# neopixel_board2.net
KiCad netlist of a schematic drawn in EAGLE
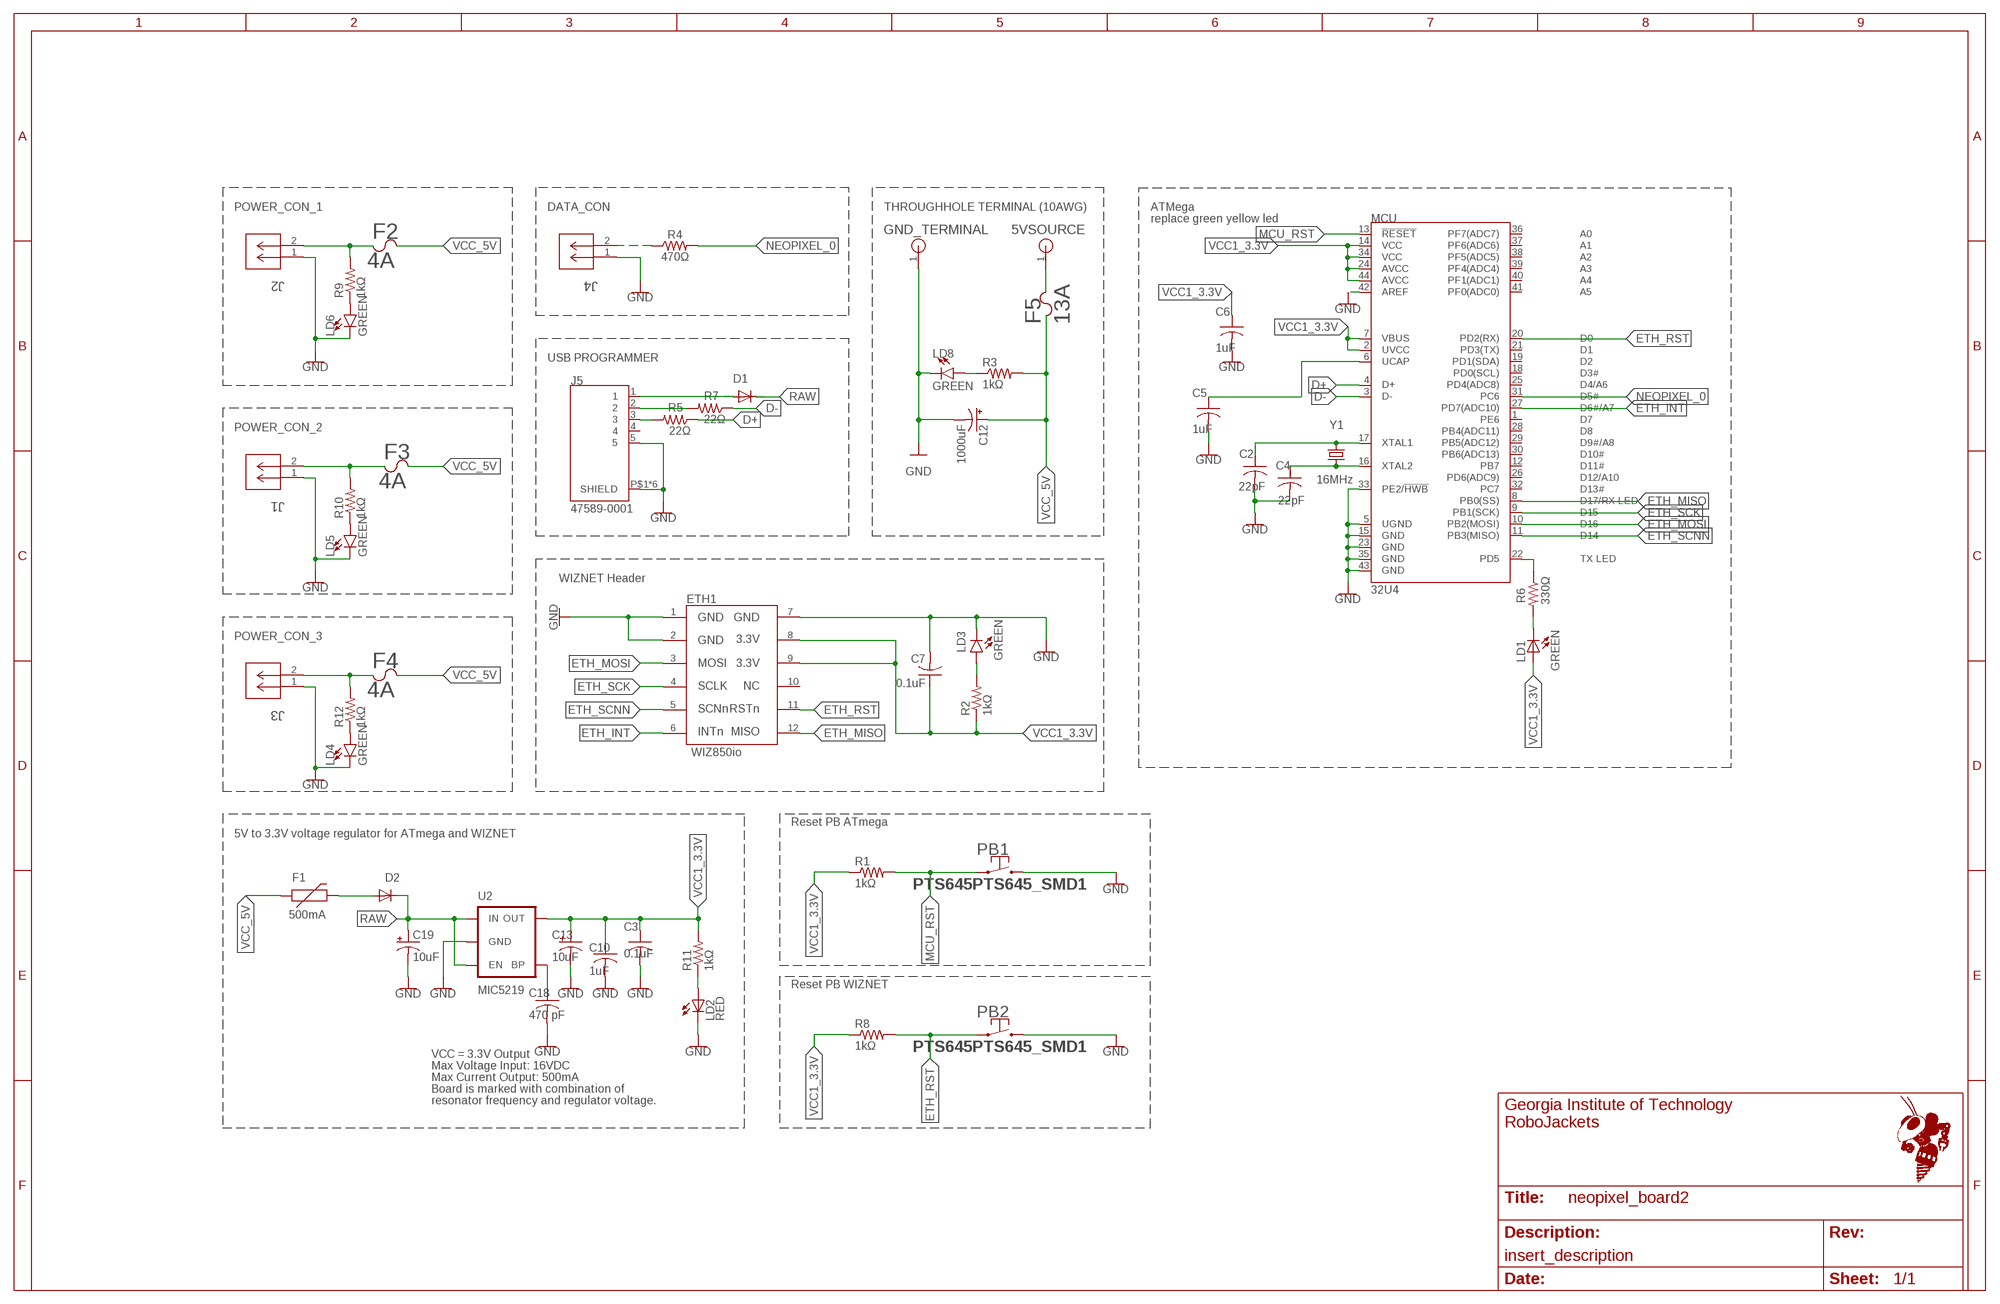
[diagram p0: schematic, sheet 1]

(export (version "E")
  (design (tool "Eeschema 10.0.6"))
  (components
    (comp (ref "5VSOURCE")
      (value "THOLE_SOURCE")
      (footprint "eagle-import:THOLE_SOURCE")
      (libsource (lib "eagle-import") (part "THOLE_SOURCE"))
    )
    (comp (ref "C2")
      (value "22pF")
      (footprint "eagle-import:C0603")
      (libsource (lib "eagle-import") (part "C-USC0603"))
    )
    (comp (ref "C3")
      (value "0.1uF")
      (footprint "eagle-import:C0603")
      (libsource (lib "eagle-import") (part "C-USC0603"))
    )
    (comp (ref "C4")
      (value "22pF")
      (footprint "eagle-import:C0603")
      (libsource (lib "eagle-import") (part "C-USC0603"))
    )
    (comp (ref "C5")
      (value "1uF")
      (footprint "eagle-import:C0603")
      (libsource (lib "eagle-import") (part "C-USC0603"))
    )
    (comp (ref "C6")
      (value "1uF")
      (footprint "eagle-import:C0603")
      (libsource (lib "eagle-import") (part "C-USC0603"))
    )
    (comp (ref "C7")
      (value "0.1uF")
      (footprint "eagle-import:C0603")
      (fields (field (name "SPICEPREFIX") "0.1 uF"))
      (libsource (lib "eagle-import") (part "C-USC0603"))
    )
    (comp (ref "C10")
      (value "1uF")
      (footprint "eagle-import:C0603")
      (libsource (lib "eagle-import") (part "C-USC0603"))
    )
    (comp (ref "C12")
      (value "1000uF")
      (footprint "eagle-import:EIA3216")
      (libsource (lib "eagle-import") (part "CAP_POL1206"))
    )
    (comp (ref "C13")
      (value "10uF")
      (footprint "eagle-import:EIA3216")
      (libsource (lib "eagle-import") (part "CAP_POL1206"))
    )
    (comp (ref "C18")
      (value "470 pF")
      (footprint "eagle-import:C0603")
      (fields (field (name "SPICEPREFIX") "0.1 uF"))
      (libsource (lib "eagle-import") (part "C-USC0603"))
    )
    (comp (ref "C19")
      (value "10uF")
      (footprint "eagle-import:EIA3216")
      (libsource (lib "eagle-import") (part "CAP_POL1206"))
    )
    (comp (ref "D1")
      (value "DIODE-SOD110-W")
      (footprint "eagle-import:SOD110-W")
      (libsource (lib "eagle-import") (part "DIODE-SOD110-W"))
    )
    (comp (ref "D2")
      (value "DIODESOD")
      (footprint "eagle-import:SOD-323")
      (libsource (lib "eagle-import") (part "DIODESOD"))
    )
    (comp (ref "ETH1")
      (value "WIZ850IO")
      (footprint "eagle-import:WIZ850IO")
      (libsource (lib "eagle-import") (part "WIZ850IO"))
    )
    (comp (ref "F1")
      (value "500mA")
      (footprint "eagle-import:PTC-1206")
      (libsource (lib "eagle-import") (part "PTCSMD"))
    )
    (comp (ref "F2")
      (value "4A")
      (footprint "eagle-import:3557-2")
      (fields (field (name "MPN") "3557-2"))
      (libsource (lib "eagle-import") (part "3557-2"))
    )
    (comp (ref "F3")
      (value "4A")
      (footprint "eagle-import:3557-2")
      (fields (field (name "MPN") "3557-2"))
      (libsource (lib "eagle-import") (part "3557-2"))
    )
    (comp (ref "F4")
      (value "4A")
      (footprint "eagle-import:3557-2")
      (fields (field (name "MPN") "3557-2"))
      (libsource (lib "eagle-import") (part "3557-2"))
    )
    (comp (ref "F5")
      (value "13A")
      (footprint "eagle-import:3557-2")
      (fields (field (name "MPN") "3557-2"))
      (libsource (lib "eagle-import") (part "3557-2"))
    )
    (comp (ref "GND_TERMINAL")
      (value "THOLE_SOURCE")
      (footprint "eagle-import:THOLE_SOURCE")
      (libsource (lib "eagle-import") (part "THOLE_SOURCE"))
    )
    (comp (ref "J1")
      (value "SSW-102-02-T-S-RA")
      (footprint "eagle-import:CON2_1X2_TR_SSQ")
      (fields (field (name "MANUFACTURER_PART_NUMBER") "SSW10202TSRA"))
      (libsource (lib "eagle-import") (part "SSW-102-02-T-S-RA"))
    )
    (comp (ref "J2")
      (value "SSW-102-02-T-S-RA")
      (footprint "eagle-import:CON2_1X2_TR_SSQ")
      (fields (field (name "MANUFACTURER_PART_NUMBER") "SSW10202TSRA"))
      (libsource (lib "eagle-import") (part "SSW-102-02-T-S-RA"))
    )
    (comp (ref "J3")
      (value "SSW-102-02-T-S-RA")
      (footprint "eagle-import:CON2_1X2_TR_SSQ")
      (fields (field (name "MANUFACTURER_PART_NUMBER") "SSW10202TSRA"))
      (libsource (lib "eagle-import") (part "SSW-102-02-T-S-RA"))
    )
    (comp (ref "J4")
      (value "SSW-102-02-T-S-RA")
      (footprint "eagle-import:CON2_1X2_TR_SSQ")
      (fields (field (name "MANUFACTURER_PART_NUMBER") "SSW10202TSRA"))
      (libsource (lib "eagle-import") (part "SSW-102-02-T-S-RA"))
    )
    (comp (ref "J5")
      (value "47589-0001")
      (footprint "eagle-import:MOLEX_47589-0001")
      (fields (field (name "MF") "Molex"))
      (libsource (lib "eagle-import") (part "47589-0001"))
    )
    (comp (ref "LD1")
      (value "GREEN")
      (footprint "eagle-import:LED-0603")
      (libsource (lib "eagle-import") (part "LED0603"))
    )
    (comp (ref "LD2")
      (value "RED")
      (footprint "eagle-import:LED-0603")
      (libsource (lib "eagle-import") (part "LED0603"))
    )
    (comp (ref "LD3")
      (value "GREEN")
      (footprint "eagle-import:LED-0603")
      (libsource (lib "eagle-import") (part "LED-GREEN0603"))
    )
    (comp (ref "LD4")
      (value "GREEN")
      (footprint "eagle-import:LED-0603")
      (libsource (lib "eagle-import") (part "LED-GREEN0603"))
    )
    (comp (ref "LD5")
      (value "GREEN")
      (footprint "eagle-import:LED-0603")
      (libsource (lib "eagle-import") (part "LED-GREEN0603"))
    )
    (comp (ref "LD6")
      (value "GREEN")
      (footprint "eagle-import:LED-0603")
      (libsource (lib "eagle-import") (part "LED-GREEN0603"))
    )
    (comp (ref "LD8")
      (value "GREEN")
      (footprint "eagle-import:LED-0603")
      (libsource (lib "eagle-import") (part "LED-GREEN0603"))
    )
    (comp (ref "MCU")
      (value "32U4")
      (footprint "eagle-import:TQFP44")
      (libsource (lib "eagle-import") (part "ATMEGA32U4TQFP-44"))
    )
    (comp (ref "PB1")
      (value "PTS645PTS645_SMD1")
      (footprint "eagle-import:PTS645_SMD")
      (libsource (lib "eagle-import") (part "PTS645PTS645_SMD1"))
    )
    (comp (ref "PB2")
      (value "PTS645PTS645_SMD1")
      (footprint "eagle-import:PTS645_SMD")
      (libsource (lib "eagle-import") (part "PTS645PTS645_SMD1"))
    )
    (comp (ref "R1")
      (value "1kΩ")
      (footprint "eagle-import:R0603")
      (libsource (lib "eagle-import") (part "R-US_R0603"))
    )
    (comp (ref "R2")
      (value "1kΩ")
      (footprint "eagle-import:R0603")
      (fields (field (name "SPICEPREFIX") "1k"))
      (libsource (lib "eagle-import") (part "R-US_R0603"))
    )
    (comp (ref "R3")
      (value "1kΩ")
      (footprint "eagle-import:0603-RES")
      (libsource (lib "eagle-import") (part "RESISTOR0603-RES"))
    )
    (comp (ref "R4")
      (value "470Ω")
      (footprint "eagle-import:0603")
      (libsource (lib "eagle-import") (part "470OHM-0603-1/10W-1%"))
    )
    (comp (ref "R5")
      (value "22Ω")
      (footprint "eagle-import:0603-RES")
      (libsource (lib "eagle-import") (part "RESISTOR0603-RES"))
    )
    (comp (ref "R6")
      (value "330Ω")
      (footprint "eagle-import:0603-RES")
      (libsource (lib "eagle-import") (part "RESISTOR0603-RES"))
    )
    (comp (ref "R7")
      (value "22Ω")
      (footprint "eagle-import:0603-RES")
      (libsource (lib "eagle-import") (part "RESISTOR0603-RES"))
    )
    (comp (ref "R8")
      (value "1kΩ")
      (footprint "eagle-import:R0603")
      (libsource (lib "eagle-import") (part "R-US_R0603"))
    )
    (comp (ref "R9")
      (value "1kΩ")
      (footprint "eagle-import:0603-RES")
      (libsource (lib "eagle-import") (part "RESISTOR0603-RES"))
    )
    (comp (ref "R10")
      (value "1kΩ")
      (footprint "eagle-import:0603-RES")
      (libsource (lib "eagle-import") (part "RESISTOR0603-RES"))
    )
    (comp (ref "R11")
      (value "1kΩ")
      (footprint "eagle-import:0603-RES")
      (libsource (lib "eagle-import") (part "RESISTOR0603-RES"))
    )
    (comp (ref "R12")
      (value "1kΩ")
      (footprint "eagle-import:0603-RES")
      (libsource (lib "eagle-import") (part "RESISTOR0603-RES"))
    )
    (comp (ref "U2")
      (value "MIC5219")
      (footprint "eagle-import:SOT23-5")
      (libsource (lib "eagle-import") (part "V_REG_LDOSMD"))
    )
    (comp (ref "Y1")
      (value "16MHz")
      (footprint "eagle-import:CRYSTAL-SMD-5X3")
      (libsource (lib "eagle-import") (part "CRYSTAL5X3"))
    )
  )
  (nets
    (net (code "1") (name "D+") (class "Default")
      (node (ref "MCU") (pin "4") (pinfunction "D+_4") (pintype "bidirectional"))
      (node (ref "R5") (pin "1") (pinfunction "1_1") (pintype "passive"))
    )
    (net (code "2") (name "D-") (class "Default")
      (node (ref "MCU") (pin "3") (pinfunction "D-_3") (pintype "bidirectional"))
      (node (ref "R7") (pin "1") (pinfunction "1_1") (pintype "passive"))
    )
    (net (code "3") (name "ETH_INT") (class "Default")
      (node (ref "ETH1") (pin "6") (pinfunction "6_6") (pintype "bidirectional"))
      (node (ref "MCU") (pin "27") (pinfunction "PD7(ADC10)_27") (pintype "bidirectional"))
    )
    (net (code "4") (name "ETH_MISO") (class "Default")
      (node (ref "ETH1") (pin "12") (pinfunction "12_12") (pintype "bidirectional"))
      (node (ref "MCU") (pin "8") (pinfunction "PB0(SS)_8") (pintype "bidirectional"))
    )
    (net (code "5") (name "ETH_MOSI") (class "Default")
      (node (ref "ETH1") (pin "3") (pinfunction "3_3") (pintype "bidirectional"))
      (node (ref "MCU") (pin "10") (pinfunction "PB2(MOSI)_10") (pintype "bidirectional"))
    )
    (net (code "6") (name "ETH_RST") (class "Default")
      (node (ref "ETH1") (pin "11") (pinfunction "11_11") (pintype "bidirectional"))
      (node (ref "MCU") (pin "20") (pinfunction "PD2(RX)_20") (pintype "bidirectional"))
      (node (ref "PB2") (pin "P$1") (pinfunction "1_P$1") (pintype "passive"))
      (node (ref "PB2") (pin "P$2") (pinfunction "1_P$2") (pintype "passive"))
      (node (ref "R8") (pin "2") (pinfunction "2_2") (pintype "passive"))
    )
    (net (code "7") (name "ETH_SCK") (class "Default")
      (node (ref "ETH1") (pin "4") (pinfunction "4_4") (pintype "bidirectional"))
      (node (ref "MCU") (pin "9") (pinfunction "PB1(SCK)_9") (pintype "bidirectional"))
    )
    (net (code "8") (name "ETH_SCNN") (class "Default")
      (node (ref "ETH1") (pin "5") (pinfunction "5_5") (pintype "bidirectional"))
      (node (ref "MCU") (pin "11") (pinfunction "PB3(MISO)_11") (pintype "bidirectional"))
    )
    (net (code "9") (name "GND") (class "Default")
      (node (ref "C10") (pin "2") (pinfunction "2_2") (pintype "passive"))
      (node (ref "C12") (pin "C") (pinfunction "-_C") (pintype "passive"))
      (node (ref "C13") (pin "C") (pinfunction "-_C") (pintype "passive"))
      (node (ref "C18") (pin "2") (pinfunction "2_2") (pintype "passive"))
      (node (ref "C19") (pin "C") (pinfunction "-_C") (pintype "passive"))
      (node (ref "C2") (pin "2") (pinfunction "2_2") (pintype "passive"))
      (node (ref "C3") (pin "2") (pinfunction "2_2") (pintype "passive"))
      (node (ref "C4") (pin "2") (pinfunction "2_2") (pintype "passive"))
      (node (ref "C5") (pin "2") (pinfunction "2_2") (pintype "passive"))
      (node (ref "C6") (pin "2") (pinfunction "2_2") (pintype "passive"))
      (node (ref "C7") (pin "2") (pinfunction "2_2") (pintype "passive"))
      (node (ref "ETH1") (pin "1") (pinfunction "1_1") (pintype "bidirectional"))
      (node (ref "ETH1") (pin "2") (pinfunction "2_2") (pintype "bidirectional"))
      (node (ref "ETH1") (pin "7") (pinfunction "7_7") (pintype "bidirectional"))
      (node (ref "GND_TERMINAL") (pin "1") (pinfunction "1_1") (pintype "passive"))
      (node (ref "J1") (pin "1") (pinfunction "1_1") (pintype "passive"))
      (node (ref "J2") (pin "1") (pinfunction "1_1") (pintype "passive"))
      (node (ref "J3") (pin "1") (pinfunction "1_1") (pintype "passive"))
      (node (ref "J4") (pin "1") (pinfunction "1_1") (pintype "passive"))
      (node (ref "J5") (pin "5") (pinfunction "5_5") (pintype "passive"))
      (node (ref "J5") (pin "P$1") (pinfunction "SHIELD_P$1") (pintype "passive"))
      (node (ref "J5") (pin "P$2") (pinfunction "SHIELD_P$2") (pintype "passive"))
      (node (ref "J5") (pin "P$3") (pinfunction "SHIELD_P$3") (pintype "passive"))
      (node (ref "J5") (pin "P$4") (pinfunction "SHIELD_P$4") (pintype "passive"))
      (node (ref "J5") (pin "P$5") (pinfunction "SHIELD_P$5") (pintype "passive"))
      (node (ref "J5") (pin "P$6") (pinfunction "SHIELD_P$6") (pintype "passive"))
      (node (ref "LD2") (pin "C") (pinfunction "C_C") (pintype "passive"))
      (node (ref "LD3") (pin "C") (pinfunction "C_C") (pintype "passive"))
      (node (ref "LD4") (pin "C") (pinfunction "C_C") (pintype "passive"))
      (node (ref "LD5") (pin "C") (pinfunction "C_C") (pintype "passive"))
      (node (ref "LD6") (pin "C") (pinfunction "C_C") (pintype "passive"))
      (node (ref "LD8") (pin "C") (pinfunction "C_C") (pintype "passive"))
      (node (ref "MCU") (pin "15") (pinfunction "GND_15") (pintype "bidirectional"))
      (node (ref "MCU") (pin "23") (pinfunction "GND_23") (pintype "bidirectional"))
      (node (ref "MCU") (pin "33") (pinfunction "PE2/~{HWB}_33") (pintype "bidirectional"))
      (node (ref "MCU") (pin "35") (pinfunction "GND_35") (pintype "bidirectional"))
      (node (ref "MCU") (pin "42") (pinfunction "AREF_42") (pintype "bidirectional"))
      (node (ref "MCU") (pin "43") (pinfunction "GND_43") (pintype "bidirectional"))
      (node (ref "MCU") (pin "5") (pinfunction "UGND_5") (pintype "bidirectional"))
      (node (ref "PB1") (pin "P$3") (pinfunction "2_P$3") (pintype "passive"))
      (node (ref "PB1") (pin "P$4") (pinfunction "2_P$4") (pintype "passive"))
      (node (ref "PB2") (pin "P$3") (pinfunction "2_P$3") (pintype "passive"))
      (node (ref "PB2") (pin "P$4") (pinfunction "2_P$4") (pintype "passive"))
      (node (ref "U2") (pin "2") (pinfunction "GND_2") (pintype "input"))
    )
    (net (code "10") (name "MCU_RST") (class "Default")
      (node (ref "MCU") (pin "13") (pinfunction "~{RESET}_13") (pintype "bidirectional"))
      (node (ref "PB1") (pin "P$1") (pinfunction "1_P$1") (pintype "passive"))
      (node (ref "PB1") (pin "P$2") (pinfunction "1_P$2") (pintype "passive"))
      (node (ref "R1") (pin "2") (pinfunction "2_2") (pintype "passive"))
    )
    (net (code "11") (name "NEOPIXEL_0") (class "Default")
      (node (ref "MCU") (pin "31") (pinfunction "PC6_31") (pintype "bidirectional"))
      (node (ref "R4") (pin "2") (pinfunction "2_2") (pintype "passive"))
    )
    (net (code "12") (name "Net-(5VSOURCE-Pad1)") (class "Default")
      (node (ref "5VSOURCE") (pin "1") (pinfunction "1_1") (pintype "passive"))
      (node (ref "F5") (pin "1") (pinfunction "1_1") (pintype "bidirectional"))
      (node (ref "F5") (pin "2") (pinfunction "1_2") (pintype "bidirectional"))
    )
    (net (code "13") (name "Net-(D1-PadA)") (class "Default")
      (node (ref "D1") (pin "A") (pinfunction "A_A") (pintype "passive"))
      (node (ref "J5") (pin "1") (pinfunction "1_1") (pintype "passive"))
    )
    (net (code "14") (name "Net-(D2-A)") (class "Default")
      (node (ref "D2") (pin "2") (pinfunction "A_2") (pintype "passive"))
      (node (ref "F1") (pin "2") (pinfunction "2_2") (pintype "bidirectional"))
    )
    (net (code "15") (name "Net-(F2-1-Pad2)") (class "Default")
      (node (ref "F2") (pin "1") (pinfunction "1_1") (pintype "bidirectional"))
      (node (ref "F2") (pin "2") (pinfunction "1_2") (pintype "bidirectional"))
      (node (ref "J2") (pin "2") (pinfunction "2_2") (pintype "passive"))
      (node (ref "R9") (pin "2") (pinfunction "2_2") (pintype "passive"))
    )
    (net (code "16") (name "Net-(F3-1-Pad2)") (class "Default")
      (node (ref "F3") (pin "1") (pinfunction "1_1") (pintype "bidirectional"))
      (node (ref "F3") (pin "2") (pinfunction "1_2") (pintype "bidirectional"))
      (node (ref "J1") (pin "2") (pinfunction "2_2") (pintype "passive"))
      (node (ref "R10") (pin "2") (pinfunction "2_2") (pintype "passive"))
    )
    (net (code "17") (name "Net-(F4-1-Pad2)") (class "Default")
      (node (ref "F4") (pin "1") (pinfunction "1_1") (pintype "bidirectional"))
      (node (ref "F4") (pin "2") (pinfunction "1_2") (pintype "bidirectional"))
      (node (ref "J3") (pin "2") (pinfunction "2_2") (pintype "passive"))
      (node (ref "R12") (pin "2") (pinfunction "2_2") (pintype "passive"))
    )
    (net (code "18") (name "Net-(J4-Pad2)") (class "Default")
      (node (ref "J4") (pin "2") (pinfunction "2_2") (pintype "passive"))
      (node (ref "R4") (pin "1") (pinfunction "1_1") (pintype "passive"))
    )
    (net (code "19") (name "Net-(J5-Pad2)") (class "Default")
      (node (ref "J5") (pin "2") (pinfunction "2_2") (pintype "passive"))
      (node (ref "R7") (pin "2") (pinfunction "2_2") (pintype "passive"))
    )
    (net (code "20") (name "Net-(J5-Pad3)") (class "Default")
      (node (ref "J5") (pin "3") (pinfunction "3_3") (pintype "passive"))
      (node (ref "R5") (pin "2") (pinfunction "2_2") (pintype "passive"))
    )
    (net (code "21") (name "Net-(LD1-PadC)") (class "Default")
      (node (ref "LD1") (pin "C") (pinfunction "C_C") (pintype "passive"))
      (node (ref "R6") (pin "2") (pinfunction "2_2") (pintype "passive"))
    )
    (net (code "22") (name "Net-(LD2-PadA)") (class "Default")
      (node (ref "LD2") (pin "A") (pinfunction "A_A") (pintype "passive"))
      (node (ref "R11") (pin "1") (pinfunction "1_1") (pintype "passive"))
    )
    (net (code "23") (name "Net-(LD3-PadA)") (class "Default")
      (node (ref "LD3") (pin "A") (pinfunction "A_A") (pintype "passive"))
      (node (ref "R2") (pin "2") (pinfunction "2_2") (pintype "passive"))
    )
    (net (code "24") (name "Net-(LD4-PadA)") (class "Default")
      (node (ref "LD4") (pin "A") (pinfunction "A_A") (pintype "passive"))
      (node (ref "R12") (pin "1") (pinfunction "1_1") (pintype "passive"))
    )
    (net (code "25") (name "Net-(LD5-PadA)") (class "Default")
      (node (ref "LD5") (pin "A") (pinfunction "A_A") (pintype "passive"))
      (node (ref "R10") (pin "1") (pinfunction "1_1") (pintype "passive"))
    )
    (net (code "26") (name "Net-(LD6-PadA)") (class "Default")
      (node (ref "LD6") (pin "A") (pinfunction "A_A") (pintype "passive"))
      (node (ref "R9") (pin "1") (pinfunction "1_1") (pintype "passive"))
    )
    (net (code "27") (name "Net-(LD8-PadA)") (class "Default")
      (node (ref "LD8") (pin "A") (pinfunction "A_A") (pintype "passive"))
      (node (ref "R3") (pin "1") (pinfunction "1_1") (pintype "passive"))
    )
    (net (code "28") (name "Net-(MCU-PD5)") (class "Default")
      (node (ref "MCU") (pin "22") (pinfunction "PD5_22") (pintype "bidirectional"))
      (node (ref "R6") (pin "1") (pinfunction "1_1") (pintype "passive"))
    )
    (net (code "29") (name "Net-(MCU-UCAP)") (class "Default")
      (node (ref "C5") (pin "1") (pinfunction "1_1") (pintype "passive"))
      (node (ref "MCU") (pin "6") (pinfunction "UCAP_6") (pintype "bidirectional"))
    )
    (net (code "30") (name "Net-(MCU-XTAL1)") (class "Default")
      (node (ref "C2") (pin "1") (pinfunction "1_1") (pintype "passive"))
      (node (ref "MCU") (pin "17") (pinfunction "XTAL1_17") (pintype "bidirectional"))
      (node (ref "Y1") (pin "3") (pinfunction "2_3") (pintype "passive"))
    )
    (net (code "31") (name "Net-(MCU-XTAL2)") (class "Default")
      (node (ref "C4") (pin "1") (pinfunction "1_1") (pintype "passive"))
      (node (ref "MCU") (pin "16") (pinfunction "XTAL2_16") (pintype "bidirectional"))
      (node (ref "Y1") (pin "1") (pinfunction "1_1") (pintype "passive"))
    )
    (net (code "32") (name "Net-(U2-BP)") (class "Default")
      (node (ref "C18") (pin "1") (pinfunction "1_1") (pintype "passive"))
      (node (ref "U2") (pin "4") (pinfunction "BP_4") (pintype "input"))
    )
    (net (code "33") (name "RAW") (class "Default")
      (node (ref "C19") (pin "A") (pinfunction "+_A") (pintype "passive"))
      (node (ref "D1") (pin "C") (pinfunction "C_C") (pintype "passive"))
      (node (ref "D2") (pin "1") (pinfunction "C_1") (pintype "passive"))
      (node (ref "U2") (pin "1") (pinfunction "IN_1") (pintype "input"))
      (node (ref "U2") (pin "3") (pinfunction "EN_3") (pintype "input"))
    )
    (net (code "34") (name "VCC1_3.3V") (class "Default")
      (node (ref "C10") (pin "1") (pinfunction "1_1") (pintype "passive"))
      (node (ref "C13") (pin "A") (pinfunction "+_A") (pintype "passive"))
      (node (ref "C3") (pin "1") (pinfunction "1_1") (pintype "passive"))
      (node (ref "C6") (pin "1") (pinfunction "1_1") (pintype "passive"))
      (node (ref "C7") (pin "1") (pinfunction "1_1") (pintype "passive"))
      (node (ref "ETH1") (pin "8") (pinfunction "8_8") (pintype "bidirectional"))
      (node (ref "ETH1") (pin "9") (pinfunction "9_9") (pintype "bidirectional"))
      (node (ref "LD1") (pin "A") (pinfunction "A_A") (pintype "passive"))
      (node (ref "MCU") (pin "14") (pinfunction "VCC_14") (pintype "bidirectional"))
      (node (ref "MCU") (pin "2") (pinfunction "UVCC_2") (pintype "bidirectional"))
      (node (ref "MCU") (pin "24") (pinfunction "AVCC_24") (pintype "bidirectional"))
      (node (ref "MCU") (pin "34") (pinfunction "VCC_34") (pintype "bidirectional"))
      (node (ref "MCU") (pin "44") (pinfunction "AVCC_44") (pintype "bidirectional"))
      (node (ref "MCU") (pin "7") (pinfunction "VBUS_7") (pintype "bidirectional"))
      (node (ref "R1") (pin "1") (pinfunction "1_1") (pintype "passive"))
      (node (ref "R11") (pin "2") (pinfunction "2_2") (pintype "passive"))
      (node (ref "R2") (pin "1") (pinfunction "1_1") (pintype "passive"))
      (node (ref "R8") (pin "1") (pinfunction "1_1") (pintype "passive"))
      (node (ref "U2") (pin "5") (pinfunction "OUT_5") (pintype "passive"))
    )
    (net (code "35") (name "VCC_5V") (class "Default")
      (node (ref "C12") (pin "A") (pinfunction "+_A") (pintype "passive"))
      (node (ref "F1") (pin "1") (pinfunction "1_1") (pintype "bidirectional"))
      (node (ref "F2") (pin "3") (pinfunction "2_3") (pintype "bidirectional"))
      (node (ref "F2") (pin "4") (pinfunction "2_4") (pintype "bidirectional"))
      (node (ref "F3") (pin "3") (pinfunction "2_3") (pintype "bidirectional"))
      (node (ref "F3") (pin "4") (pinfunction "2_4") (pintype "bidirectional"))
      (node (ref "F4") (pin "3") (pinfunction "2_3") (pintype "bidirectional"))
      (node (ref "F4") (pin "4") (pinfunction "2_4") (pintype "bidirectional"))
      (node (ref "F5") (pin "3") (pinfunction "2_3") (pintype "bidirectional"))
      (node (ref "F5") (pin "4") (pinfunction "2_4") (pintype "bidirectional"))
      (node (ref "R3") (pin "2") (pinfunction "2_2") (pintype "passive"))
    )
    (net (code "36") (name "unconnected-(ETH1-Pad10)") (class "Default")
      (node (ref "ETH1") (pin "10") (pinfunction "10_10") (pintype "bidirectional"))
    )
    (net (code "37") (name "unconnected-(J5-Pad4)") (class "Default")
      (node (ref "J5") (pin "4") (pinfunction "4_4") (pintype "passive"))
    )
    (net (code "38") (name "unconnected-(MCU-PB4(ADC11)-Pad28)") (class "Default")
      (node (ref "MCU") (pin "28") (pinfunction "PB4(ADC11)_28") (pintype "bidirectional"))
    )
    (net (code "39") (name "unconnected-(MCU-PB5(ADC12)-Pad29)") (class "Default")
      (node (ref "MCU") (pin "29") (pinfunction "PB5(ADC12)_29") (pintype "bidirectional"))
    )
    (net (code "40") (name "unconnected-(MCU-PB6(ADC13)-Pad30)") (class "Default")
      (node (ref "MCU") (pin "30") (pinfunction "PB6(ADC13)_30") (pintype "bidirectional"))
    )
    (net (code "41") (name "unconnected-(MCU-PB7-Pad12)") (class "Default")
      (node (ref "MCU") (pin "12") (pinfunction "PB7_12") (pintype "bidirectional"))
    )
    (net (code "42") (name "unconnected-(MCU-PC7-Pad32)") (class "Default")
      (node (ref "MCU") (pin "32") (pinfunction "PC7_32") (pintype "bidirectional"))
    )
    (net (code "43") (name "unconnected-(MCU-PD0(SCL)-Pad18)") (class "Default")
      (node (ref "MCU") (pin "18") (pinfunction "PD0(SCL)_18") (pintype "bidirectional"))
    )
    (net (code "44") (name "unconnected-(MCU-PD1(SDA)-Pad19)") (class "Default")
      (node (ref "MCU") (pin "19") (pinfunction "PD1(SDA)_19") (pintype "bidirectional"))
    )
    (net (code "45") (name "unconnected-(MCU-PD3(TX)-Pad21)") (class "Default")
      (node (ref "MCU") (pin "21") (pinfunction "PD3(TX)_21") (pintype "bidirectional"))
    )
    (net (code "46") (name "unconnected-(MCU-PD4(ADC8)-Pad25)") (class "Default")
      (node (ref "MCU") (pin "25") (pinfunction "PD4(ADC8)_25") (pintype "bidirectional"))
    )
    (net (code "47") (name "unconnected-(MCU-PD6(ADC9)-Pad26)") (class "Default")
      (node (ref "MCU") (pin "26") (pinfunction "PD6(ADC9)_26") (pintype "bidirectional"))
    )
    (net (code "48") (name "unconnected-(MCU-PE6-Pad1)") (class "Default")
      (node (ref "MCU") (pin "1") (pinfunction "PE6_1") (pintype "bidirectional"))
    )
    (net (code "49") (name "unconnected-(MCU-PF0(ADC0)-Pad41)") (class "Default")
      (node (ref "MCU") (pin "41") (pinfunction "PF0(ADC0)_41") (pintype "bidirectional"))
    )
    (net (code "50") (name "unconnected-(MCU-PF1(ADC1)-Pad40)") (class "Default")
      (node (ref "MCU") (pin "40") (pinfunction "PF1(ADC1)_40") (pintype "bidirectional"))
    )
    (net (code "51") (name "unconnected-(MCU-PF4(ADC4)-Pad39)") (class "Default")
      (node (ref "MCU") (pin "39") (pinfunction "PF4(ADC4)_39") (pintype "bidirectional"))
    )
    (net (code "52") (name "unconnected-(MCU-PF5(ADC5)-Pad38)") (class "Default")
      (node (ref "MCU") (pin "38") (pinfunction "PF5(ADC5)_38") (pintype "bidirectional"))
    )
    (net (code "53") (name "unconnected-(MCU-PF6(ADC6)-Pad37)") (class "Default")
      (node (ref "MCU") (pin "37") (pinfunction "PF6(ADC6)_37") (pintype "bidirectional"))
    )
    (net (code "54") (name "unconnected-(MCU-PF7(ADC7)-Pad36)") (class "Default")
      (node (ref "MCU") (pin "36") (pinfunction "PF7(ADC7)_36") (pintype "bidirectional"))
    )
  )
)
